# LB_BIT_o2_LONGLED-v03_rev2.net
KiCad netlist of a schematic drawn in EAGLE
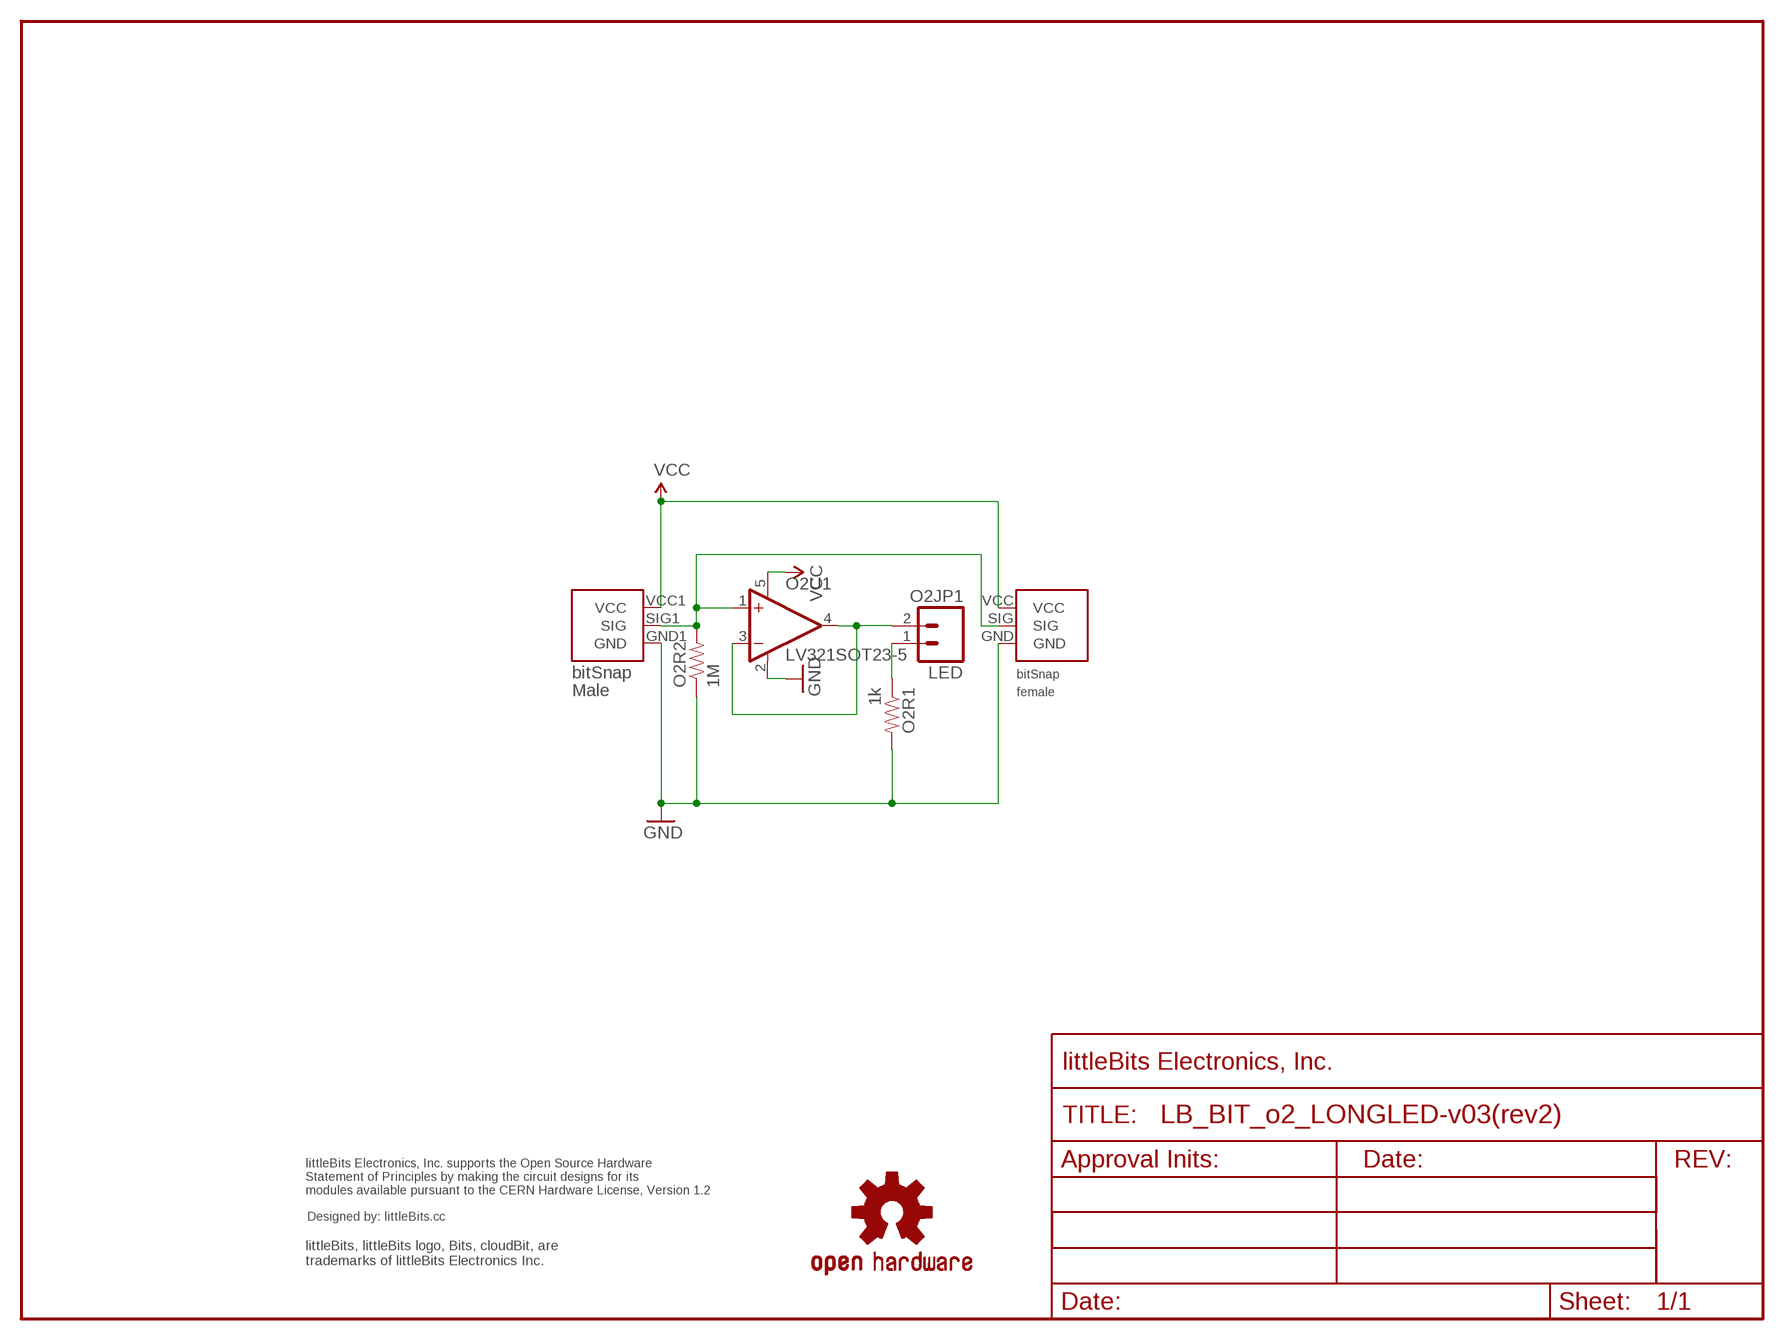
[diagram p0: schematic, sheet 1]

(export (version "E")
  (design (tool "Eeschema 10.0.6"))
  (components
    (comp (ref "O2BSF")
      (value "BITSNAP_V03_FEMALE")
      (footprint "eagle-import:BITSNAP_V03_FEMALE")
      (libsource (lib "eagle-import") (part "BITSNAP_V03_FEMALE"))
    )
    (comp (ref "O2BSM")
      (value "BITSNAP_V03_MALE")
      (footprint "eagle-import:BITSNAP_V03_MALE")
      (libsource (lib "eagle-import") (part "BITSNAP_V03_MALE"))
    )
    (comp (ref "O2JP1")
      (value "LED")
      (footprint "eagle-import:S2B-PH")
      (libsource (lib "eagle-import") (part "M02-JST-2MM-SMT"))
    )
    (comp (ref "O2R1")
      (value "1k")
      (footprint "eagle-import:0603-RES")
      (libsource (lib "eagle-import") (part "RESISTOR0603-RES"))
    )
    (comp (ref "O2R2")
      (value "1M")
      (footprint "eagle-import:0603-RES")
      (libsource (lib "eagle-import") (part "RESISTOR0603-RES"))
    )
    (comp (ref "O2U1")
      (value "LV321SOT23-5")
      (footprint "eagle-import:SOT23-5")
      (libsource (lib "eagle-import") (part "LV321SOT23-5"))
    )
    (comp (ref "U$1")
      (value "OSHWCREDIT")
      (footprint "eagle-import:OSHWCREDIT")
      (libsource (lib "eagle-import") (part "OSHWCREDIT"))
    )
    (comp (ref "U$2")
      (value "FRAME-LETTER-OHWOHW")
      (footprint "eagle-import:FABDWG01-OHW")
      (libsource (lib "eagle-import") (part "FRAME-LETTER-OHWOHW"))
    )
    (comp (ref "U$14")
      (value "OSHW-LOGOL")
      (footprint "eagle-import:OSHW-LOGO-L")
      (libsource (lib "eagle-import") (part "OSHW-LOGOL"))
    )
  )
  (nets
    (net (code "1") (name "GND") (class "Default")
      (node (ref "O2BSF") (pin "GND") (pinfunction "GND_GND") (pintype "bidirectional"))
      (node (ref "O2BSM") (pin "GND1") (pinfunction "GND_GND1") (pintype "bidirectional"))
      (node (ref "O2R1") (pin "2") (pinfunction "2_2") (pintype "passive"))
      (node (ref "O2R2") (pin "1") (pinfunction "1_1") (pintype "passive"))
      (node (ref "O2U1") (pin "2") (pinfunction "V-_2") (pintype "power_in"))
    )
    (net (code "2") (name "Net-(O2BSM-SIG)") (class "Default")
      (node (ref "O2BSF") (pin "SIG") (pinfunction "SIG_SIG") (pintype "bidirectional"))
      (node (ref "O2BSM") (pin "SIG1") (pinfunction "SIG_SIG1") (pintype "bidirectional"))
      (node (ref "O2R2") (pin "2") (pinfunction "2_2") (pintype "passive"))
      (node (ref "O2U1") (pin "1") (pinfunction "+IN_1") (pintype "input"))
    )
    (net (code "3") (name "Net-(O2JP1-Pad1)") (class "Default")
      (node (ref "O2JP1") (pin "1") (pinfunction "1_1") (pintype "passive"))
      (node (ref "O2R1") (pin "1") (pinfunction "1_1") (pintype "passive"))
    )
    (net (code "4") (name "Net-(O2U1--IN)") (class "Default")
      (node (ref "O2JP1") (pin "2") (pinfunction "2_2") (pintype "passive"))
      (node (ref "O2U1") (pin "3") (pinfunction "-IN_3") (pintype "input"))
      (node (ref "O2U1") (pin "4") (pinfunction "OUT_4") (pintype "output"))
    )
    (net (code "5") (name "VCC") (class "Default")
      (node (ref "O2BSF") (pin "VCC") (pinfunction "VCC_VCC") (pintype "bidirectional"))
      (node (ref "O2BSM") (pin "VCC1") (pinfunction "VCC_VCC1") (pintype "bidirectional"))
      (node (ref "O2U1") (pin "5") (pinfunction "V+_5") (pintype "power_in"))
    )
  )
)
